# SuperFin_Baseboard_pg6.net
KiCad netlist of a schematic drawn in Altium Designer
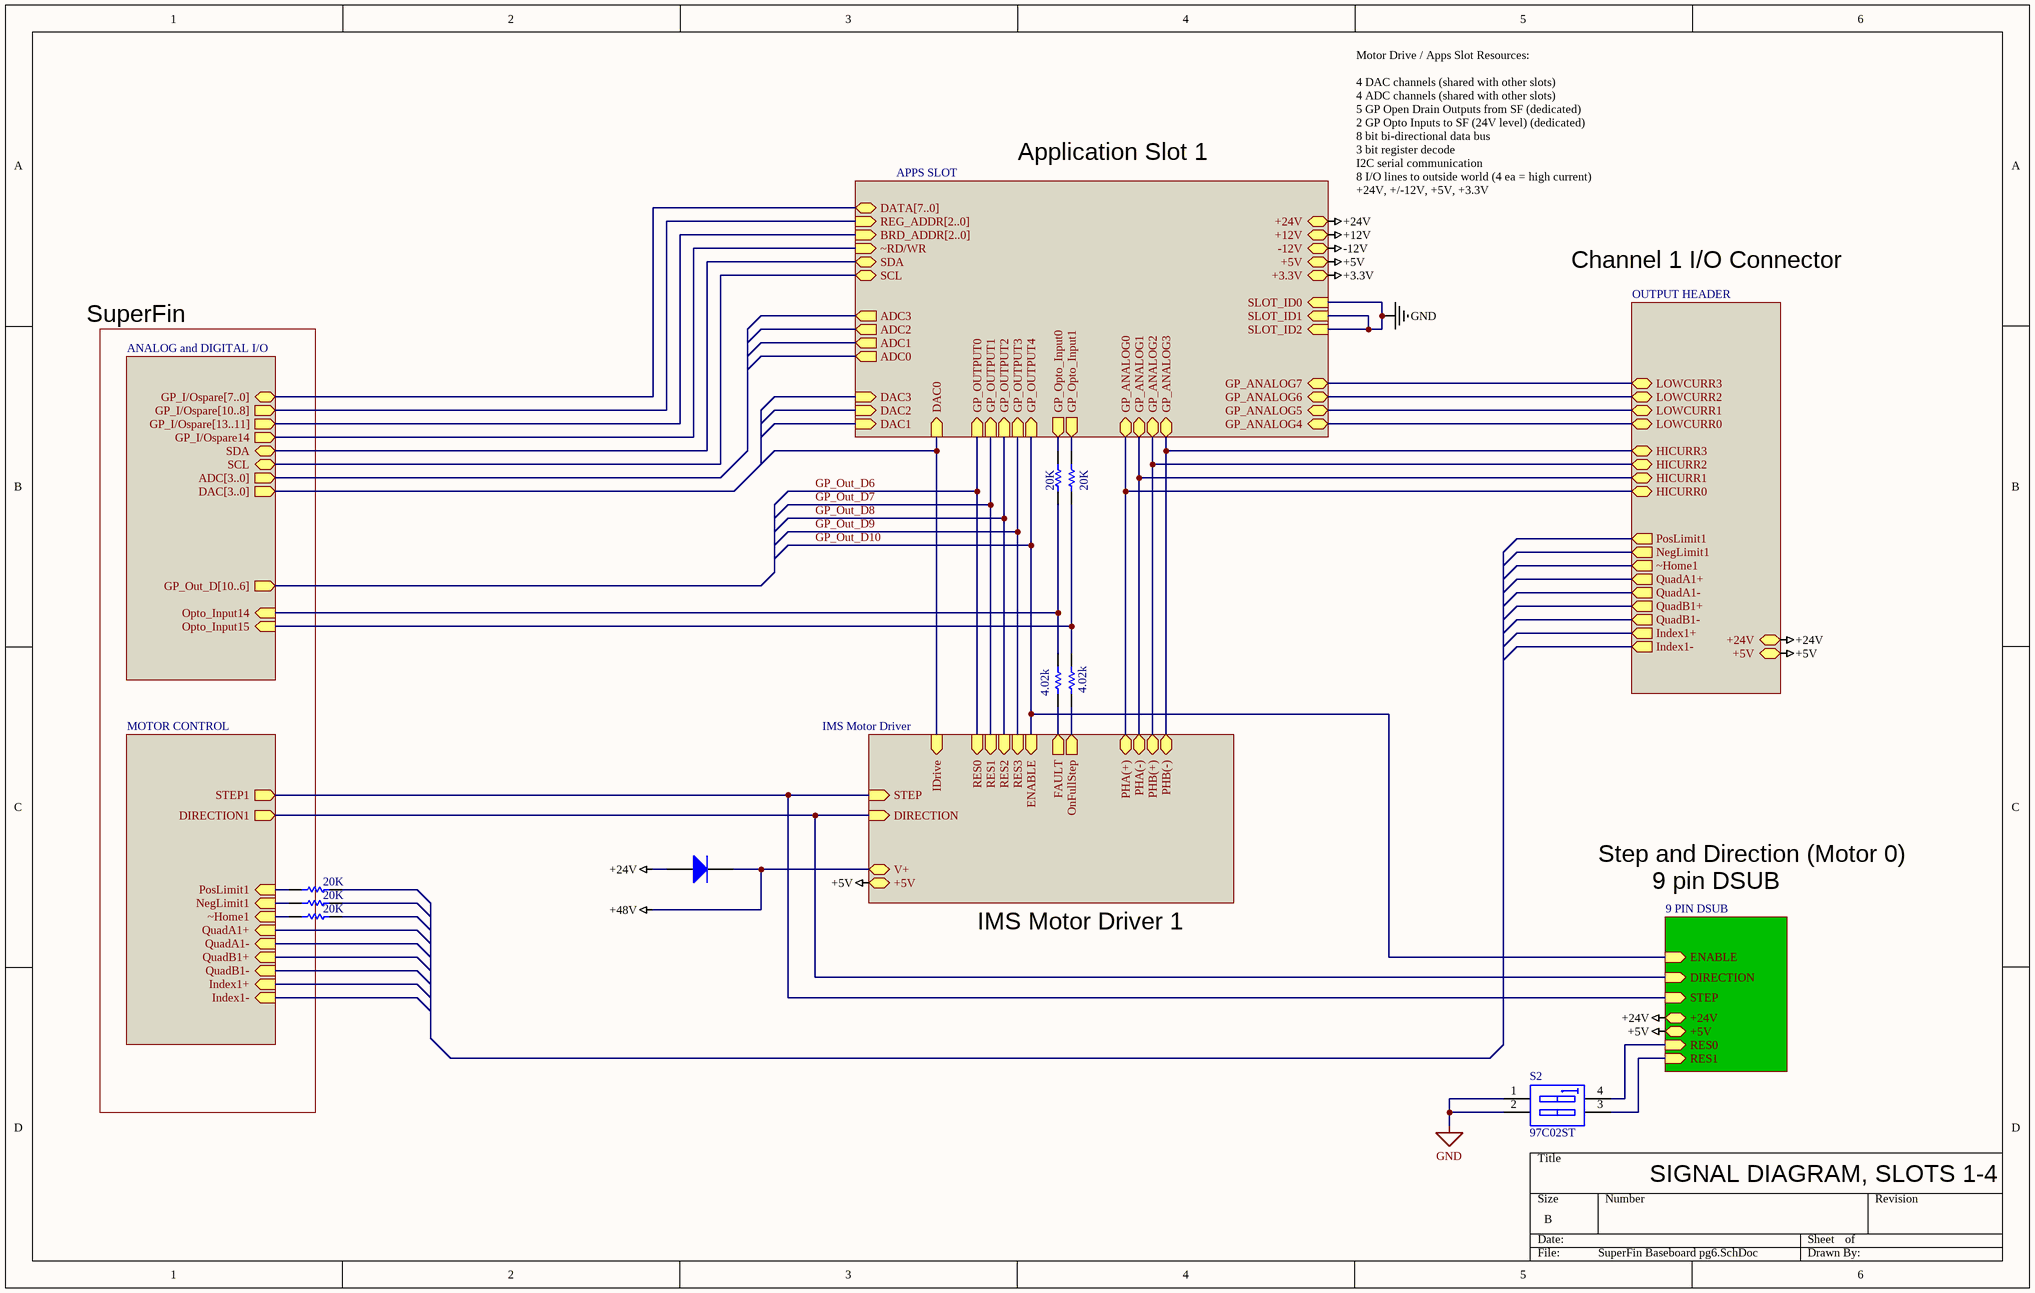
[diagram p0: SuperFin Baseboard pg6.SchDoc]

(export (version "E")
  (design (tool "Eeschema 10.0.6"))
  (components
    (comp (ref "D1")
      (value "Diode 1N4001")
      (footprint "DIO10.46-5.3x2.8")
      (description "1 Amp General Purpose Rectifier")
      (fields (field (name "PUBLISHER") "Altium Limited"))
      (libsource (lib "Miscellaneous Devices") (part "Diode 1N4001"))
    )
    (comp (ref "R10")
      (value "20K")
      (footprint "SMD_0805")
      (description "Resistor 0805")
      (fields (field (name "MANUFACTURER") "Vishay/Dale") (field (name "Comment") "Res 0805"))
      (libsource (lib "Richs Schematic Components") (part "Res SMD"))
    )
    (comp (ref "R11")
      (value "20K")
      (footprint "SMD_0805")
      (description "Resistor 0805")
      (fields (field (name "MANUFACTURER") "Vishay/Dale") (field (name "Comment") "Res 0805"))
      (libsource (lib "Richs Schematic Components") (part "Res SMD"))
    )
    (comp (ref "R12")
      (value "4.02k")
      (footprint "SMD_0805")
      (description "Resistor 0805")
      (fields (field (name "MANUFACTURER") "Vishay/Dale") (field (name "Comment") "Res 0805"))
      (libsource (lib "Richs Schematic Components") (part "Res SMD"))
    )
    (comp (ref "R13")
      (value "4.02k")
      (footprint "SMD_0805")
      (description "Resistor 0805")
      (fields (field (name "MANUFACTURER") "Vishay/Dale") (field (name "Comment") "Res 0805"))
      (libsource (lib "Richs Schematic Components") (part "Res SMD"))
    )
    (comp (ref "R14")
      (value "20K")
      (footprint "SMD_0805")
      (description "Resistor 0805")
      (fields (field (name "MANUFACTURER") "Vishay/Dale") (field (name "Comment") "Res 0805"))
      (libsource (lib "Richs Schematic Components") (part "Res SMD"))
    )
    (comp (ref "R15")
      (value "20K")
      (footprint "SMD_0805")
      (description "Resistor 0805")
      (fields (field (name "MANUFACTURER") "Vishay/Dale") (field (name "Comment") "Res 0805"))
      (libsource (lib "Richs Schematic Components") (part "Res SMD"))
    )
    (comp (ref "R16")
      (value "20K")
      (footprint "SMD_0805")
      (description "Resistor 0805")
      (fields (field (name "MANUFACTURER") "Vishay/Dale") (field (name "Comment") "Res 0805"))
      (libsource (lib "Richs Schematic Components") (part "Res SMD"))
    )
    (comp (ref "S2")
      (value "97C02ST")
      (footprint "97C02ST")
      (description "DIP Switch, 2 Position, SPST")
      (fields (field (name "MANUFACTURER") "Grayhill"))
      (libsource (lib "Miscellaneous Devices") (part "SW DIP-2"))
    )
  )
  (nets
    (net (code "4") (name "+24V") (class "Default")
      (node (ref "D1") (pin "1") (pinfunction "A_1") (pintype "passive"))
    )
    (net (code "5") (name "+48V") (class "Default")
      (node (ref "D1") (pin "2") (pinfunction "K_2") (pintype "passive"))
    )
    (net (code "19") (name "/FAULT") (class "Default")
      (node (ref "R12") (pin "1") (pinfunction "1_1") (pintype "passive"))
    )
    (net (code "31") (name "/GP_Opto_Input0") (class "Default")
      (node (ref "R10") (pin "2") (pinfunction "2_2") (pintype "passive"))
    )
    (net (code "32") (name "/GP_Opto_Input1") (class "Default")
      (node (ref "R11") (pin "1") (pinfunction "1_1") (pintype "passive"))
    )
    (net (code "44") (name "/NegLimit1_1") (class "Default")
      (node (ref "R15") (pin "1") (pinfunction "1_1") (pintype "passive"))
    )
    (net (code "45") (name "/OnFullStep") (class "Default")
      (node (ref "R13") (pin "1") (pinfunction "1_1") (pintype "passive"))
    )
    (net (code "46") (name "/Opto_Input14") (class "Default")
      (node (ref "R10") (pin "1") (pinfunction "1_1") (pintype "passive"))
      (node (ref "R12") (pin "2") (pinfunction "2_2") (pintype "passive"))
    )
    (net (code "47") (name "/Opto_Input15") (class "Default")
      (node (ref "R11") (pin "2") (pinfunction "2_2") (pintype "passive"))
      (node (ref "R13") (pin "2") (pinfunction "2_2") (pintype "passive"))
    )
    (net (code "49") (name "/PosLimit1_1") (class "Default")
      (node (ref "R14") (pin "1") (pinfunction "1_1") (pintype "passive"))
    )
    (net (code "58") (name "/RES0") (class "Default")
      (node (ref "S2") (pin "4") (pinfunction "B1_4") (pintype "passive"))
    )
    (net (code "59") (name "/RES1") (class "Default")
      (node (ref "S2") (pin "3") (pinfunction "B2_3") (pintype "passive"))
    )
    (net (code "64") (name "/~Home1_1") (class "Default")
      (node (ref "R16") (pin "1") (pinfunction "1_1") (pintype "passive"))
    )
    (net (code "65") (name "GND") (class "Default")
      (node (ref "S2") (pin "1") (pinfunction "A1_1") (pintype "passive"))
      (node (ref "S2") (pin "2") (pinfunction "A2_2") (pintype "passive"))
    )
    (net (code "66") (name "unconnected-(R14-Pad2)") (class "Default")
      (node (ref "R14") (pin "2") (pinfunction "2_2") (pintype "passive"))
    )
    (net (code "67") (name "unconnected-(R15-Pad2)") (class "Default")
      (node (ref "R15") (pin "2") (pinfunction "2_2") (pintype "passive"))
    )
    (net (code "68") (name "unconnected-(R16-Pad2)") (class "Default")
      (node (ref "R16") (pin "2") (pinfunction "2_2") (pintype "passive"))
    )
  )
)
